# W506E.net
KiCad netlist of a schematic drawn in EAGLE
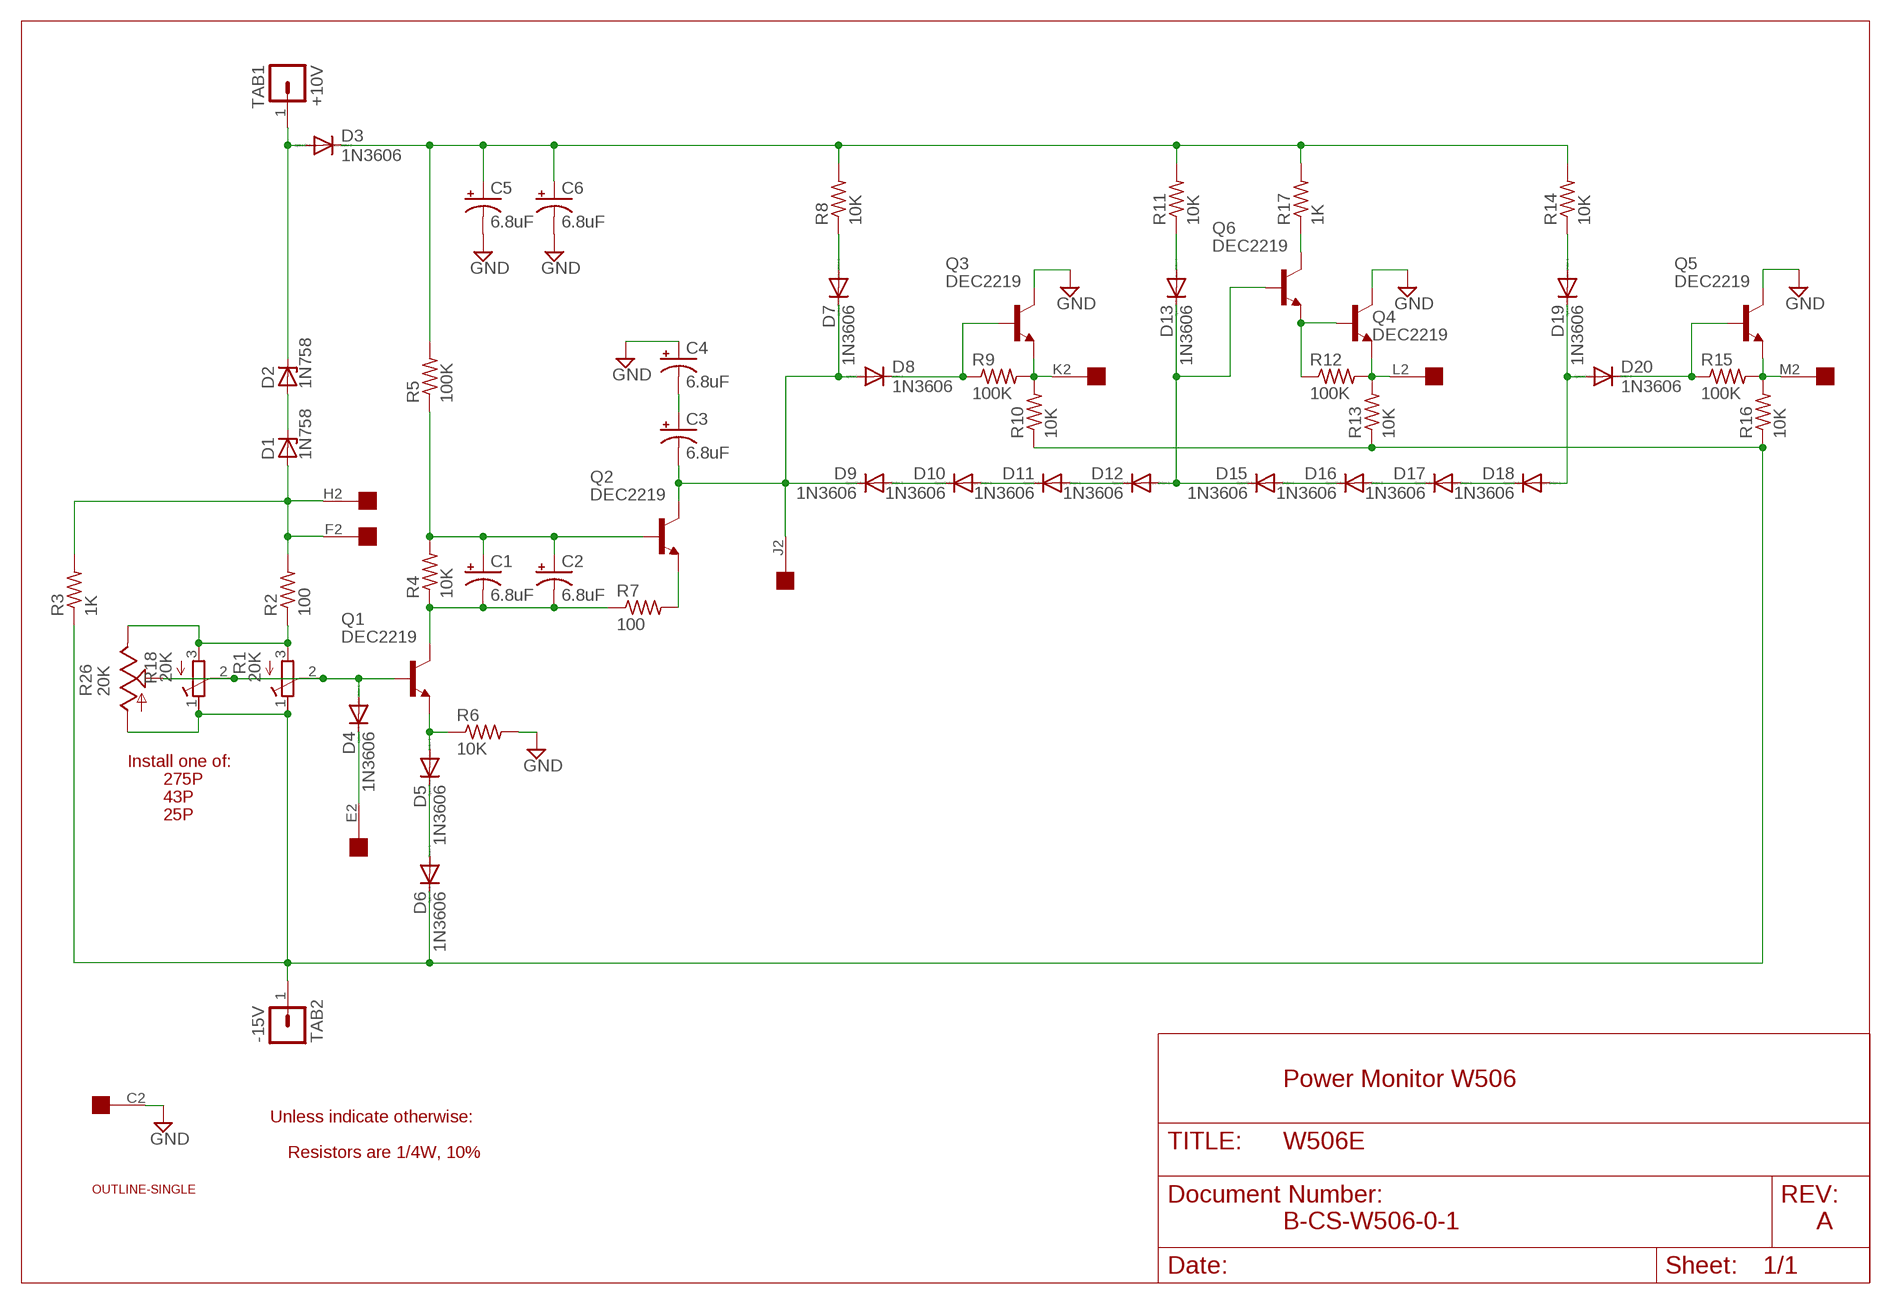
[diagram p0: schematic, sheet 1]

(export (version "E")
  (design (tool "Eeschema 10.0.6"))
  (components
    (comp (ref "C1")
      (value "6.8uF")
      (footprint "eagle-import:E15-5")
      (libsource (lib "eagle-import") (part "CPOL-USE15-5AXIAL"))
    )
    (comp (ref "C2")
      (value "6.8uF")
      (footprint "eagle-import:E15-5")
      (libsource (lib "eagle-import") (part "CPOL-USE15-5AXIAL"))
    )
    (comp (ref "C3")
      (value "6.8uF")
      (footprint "eagle-import:E15-5")
      (libsource (lib "eagle-import") (part "CPOL-USE15-5AXIAL"))
    )
    (comp (ref "C4")
      (value "6.8uF")
      (footprint "eagle-import:E15-5")
      (libsource (lib "eagle-import") (part "CPOL-USE15-5AXIAL"))
    )
    (comp (ref "C5")
      (value "6.8uF")
      (footprint "eagle-import:E15-5")
      (libsource (lib "eagle-import") (part "CPOL-USE15-5AXIAL"))
    )
    (comp (ref "C6")
      (value "6.8uF")
      (footprint "eagle-import:E15-5")
      (libsource (lib "eagle-import") (part "CPOL-USE15-5AXIAL"))
    )
    (comp (ref "D1")
      (value "1N758")
      (footprint "eagle-import:DO35Z10")
      (libsource (lib "eagle-import") (part "ZENER-DIODEDO35Z10"))
    )
    (comp (ref "D2")
      (value "1N758")
      (footprint "eagle-import:DO35Z10")
      (libsource (lib "eagle-import") (part "ZENER-DIODEDO35Z10"))
    )
    (comp (ref "D3")
      (value "1N3606")
      (footprint "eagle-import:DO35-10")
      (libsource (lib "eagle-import") (part "1N4148DO35-10"))
    )
    (comp (ref "D4")
      (value "1N3606")
      (footprint "eagle-import:DO35-10")
      (libsource (lib "eagle-import") (part "1N4148DO35-10"))
    )
    (comp (ref "D5")
      (value "1N3606")
      (footprint "eagle-import:DO35-10")
      (libsource (lib "eagle-import") (part "1N4148DO35-10"))
    )
    (comp (ref "D6")
      (value "1N3606")
      (footprint "eagle-import:DO35-10")
      (libsource (lib "eagle-import") (part "1N4148DO35-10"))
    )
    (comp (ref "D7")
      (value "1N3606")
      (footprint "eagle-import:DO35-10")
      (libsource (lib "eagle-import") (part "1N4148DO35-10"))
    )
    (comp (ref "D8")
      (value "1N3606")
      (footprint "eagle-import:DO35-10")
      (libsource (lib "eagle-import") (part "1N4148DO35-10"))
    )
    (comp (ref "D9")
      (value "1N3606")
      (footprint "eagle-import:DO35-10")
      (libsource (lib "eagle-import") (part "1N4148DO35-10"))
    )
    (comp (ref "D10")
      (value "1N3606")
      (footprint "eagle-import:DO35-10")
      (libsource (lib "eagle-import") (part "1N4148DO35-10"))
    )
    (comp (ref "D11")
      (value "1N3606")
      (footprint "eagle-import:DO35-10")
      (libsource (lib "eagle-import") (part "1N4148DO35-10"))
    )
    (comp (ref "D12")
      (value "1N3606")
      (footprint "eagle-import:DO35-10")
      (libsource (lib "eagle-import") (part "1N4148DO35-10"))
    )
    (comp (ref "D13")
      (value "1N3606")
      (footprint "eagle-import:DO35-10")
      (libsource (lib "eagle-import") (part "1N4148DO35-10"))
    )
    (comp (ref "D15")
      (value "1N3606")
      (footprint "eagle-import:DO35-10")
      (libsource (lib "eagle-import") (part "1N4148DO35-10"))
    )
    (comp (ref "D16")
      (value "1N3606")
      (footprint "eagle-import:DO35-10")
      (libsource (lib "eagle-import") (part "1N4148DO35-10"))
    )
    (comp (ref "D17")
      (value "1N3606")
      (footprint "eagle-import:DO35-10")
      (libsource (lib "eagle-import") (part "1N4148DO35-10"))
    )
    (comp (ref "D18")
      (value "1N3606")
      (footprint "eagle-import:DO35-10")
      (libsource (lib "eagle-import") (part "1N4148DO35-10"))
    )
    (comp (ref "D19")
      (value "1N3606")
      (footprint "eagle-import:DO35-10")
      (libsource (lib "eagle-import") (part "1N4148DO35-10"))
    )
    (comp (ref "D20")
      (value "1N3606")
      (footprint "eagle-import:DO35-10")
      (libsource (lib "eagle-import") (part "1N4148DO35-10"))
    )
    (comp (ref "EDGE")
      (value "EDGE-1")
      (footprint "eagle-import:EDGE-CON1")
      (libsource (lib "eagle-import") (part "EDGE-1"))
    )
    (comp (ref "Q1")
      (value "DEC2219")
      (footprint "eagle-import:TO5")
      (libsource (lib "eagle-import") (part "2N2102"))
    )
    (comp (ref "Q2")
      (value "DEC2219")
      (footprint "eagle-import:TO5")
      (libsource (lib "eagle-import") (part "2N2102"))
    )
    (comp (ref "Q3")
      (value "DEC2219")
      (footprint "eagle-import:TO5")
      (libsource (lib "eagle-import") (part "2N2102"))
    )
    (comp (ref "Q4")
      (value "DEC2219")
      (footprint "eagle-import:TO5")
      (libsource (lib "eagle-import") (part "2N2102"))
    )
    (comp (ref "Q5")
      (value "DEC2219")
      (footprint "eagle-import:TO5")
      (libsource (lib "eagle-import") (part "2N2102"))
    )
    (comp (ref "Q6")
      (value "DEC2219")
      (footprint "eagle-import:TO5")
      (libsource (lib "eagle-import") (part "2N2102"))
    )
    (comp (ref "R1")
      (value "20K")
      (footprint "eagle-import:3006Y")
      (libsource (lib "eagle-import") (part "275P"))
    )
    (comp (ref "R2")
      (value "100")
      (footprint "eagle-import:0207_10")
      (libsource (lib "eagle-import") (part "R-US_0207/10"))
    )
    (comp (ref "R3")
      (value "1K")
      (footprint "eagle-import:0207_10")
      (libsource (lib "eagle-import") (part "R-US_0207/10"))
    )
    (comp (ref "R4")
      (value "10K")
      (footprint "eagle-import:0207_10")
      (libsource (lib "eagle-import") (part "R-US_0207/10"))
    )
    (comp (ref "R5")
      (value "100K")
      (footprint "eagle-import:0207_10")
      (libsource (lib "eagle-import") (part "R-US_0207/10"))
    )
    (comp (ref "R6")
      (value "10K")
      (footprint "eagle-import:0207_10")
      (libsource (lib "eagle-import") (part "R-US_0207/10"))
    )
    (comp (ref "R7")
      (value "100")
      (footprint "eagle-import:0207_10")
      (libsource (lib "eagle-import") (part "R-US_0207/10"))
    )
    (comp (ref "R8")
      (value "10K")
      (footprint "eagle-import:0207_10")
      (libsource (lib "eagle-import") (part "R-US_0207/10"))
    )
    (comp (ref "R9")
      (value "100K")
      (footprint "eagle-import:0207_10")
      (libsource (lib "eagle-import") (part "R-US_0207/10"))
    )
    (comp (ref "R10")
      (value "10K")
      (footprint "eagle-import:0207_10")
      (libsource (lib "eagle-import") (part "R-US_0207/10"))
    )
    (comp (ref "R11")
      (value "10K")
      (footprint "eagle-import:0207_10")
      (libsource (lib "eagle-import") (part "R-US_0207/10"))
    )
    (comp (ref "R12")
      (value "100K")
      (footprint "eagle-import:0207_10")
      (libsource (lib "eagle-import") (part "R-US_0207/10"))
    )
    (comp (ref "R13")
      (value "10K")
      (footprint "eagle-import:0207_10")
      (libsource (lib "eagle-import") (part "R-US_0207/10"))
    )
    (comp (ref "R14")
      (value "10K")
      (footprint "eagle-import:0207_10")
      (libsource (lib "eagle-import") (part "R-US_0207/10"))
    )
    (comp (ref "R15")
      (value "100K")
      (footprint "eagle-import:0207_10")
      (libsource (lib "eagle-import") (part "R-US_0207/10"))
    )
    (comp (ref "R16")
      (value "10K")
      (footprint "eagle-import:0207_10")
      (libsource (lib "eagle-import") (part "R-US_0207/10"))
    )
    (comp (ref "R17")
      (value "1K")
      (footprint "eagle-import:0207_10")
      (libsource (lib "eagle-import") (part "R-US_0207/10"))
    )
    (comp (ref "R18")
      (value "20K")
      (footprint "eagle-import:RTRIM43P")
      (libsource (lib "eagle-import") (part "R-TRIMM43P"))
    )
    (comp (ref "R26")
      (value "20K")
      (footprint "eagle-import:B25P")
      (libsource (lib "eagle-import") (part "TRIM_US-B25P"))
    )
    (comp (ref "TAB1")
      (value "+10V")
      (footprint "eagle-import:SPADELUG")
      (libsource (lib "eagle-import") (part "LUG"))
    )
    (comp (ref "TAB2")
      (value "-15V")
      (footprint "eagle-import:SPADELUG")
      (libsource (lib "eagle-import") (part "LUG"))
    )
    (comp (ref "U$1")
      (value "OUTLINE-SINGLE")
      (footprint "eagle-import:SINGLE")
      (libsource (lib "eagle-import") (part "OUTLINE-SINGLE"))
    )
  )
  (nets
    (net (code "1") (name "GND") (class "Default")
      (node (ref "C4") (pin "+") (pinfunction "+_+") (pintype "passive"))
      (node (ref "C5") (pin "-") (pinfunction "-_-") (pintype "passive"))
      (node (ref "C6") (pin "-") (pinfunction "-_-") (pintype "passive"))
      (node (ref "EDGE") (pin "C2") (pinfunction "1_C2") (pintype "bidirectional"))
      (node (ref "Q3") (pin "3") (pinfunction "C_3") (pintype "passive"))
      (node (ref "Q4") (pin "3") (pinfunction "C_3") (pintype "passive"))
      (node (ref "Q5") (pin "3") (pinfunction "C_3") (pintype "passive"))
      (node (ref "R6") (pin "2") (pinfunction "2_2") (pintype "passive"))
    )
    (net (code "2") (name "Net-(C3-Pad+)") (class "Default")
      (node (ref "C3") (pin "+") (pinfunction "+_+") (pintype "passive"))
      (node (ref "C4") (pin "-") (pinfunction "-_-") (pintype "passive"))
    )
    (net (code "3") (name "Net-(C5-Pad+)") (class "Default")
      (node (ref "C5") (pin "+") (pinfunction "+_+") (pintype "passive"))
      (node (ref "C6") (pin "+") (pinfunction "+_+") (pintype "passive"))
      (node (ref "D3") (pin "C") (pinfunction "C_C") (pintype "passive"))
      (node (ref "R11") (pin "2") (pinfunction "2_2") (pintype "passive"))
      (node (ref "R14") (pin "2") (pinfunction "2_2") (pintype "passive"))
      (node (ref "R17") (pin "2") (pinfunction "2_2") (pintype "passive"))
      (node (ref "R5") (pin "2") (pinfunction "2_2") (pintype "passive"))
      (node (ref "R8") (pin "2") (pinfunction "2_2") (pintype "passive"))
    )
    (net (code "4") (name "Net-(D1-PadC)") (class "Default")
      (node (ref "D1") (pin "C") (pinfunction "C_C") (pintype "passive"))
      (node (ref "D2") (pin "A") (pinfunction "A_A") (pintype "passive"))
    )
    (net (code "5") (name "Net-(D2-PadC)") (class "Default")
      (node (ref "D2") (pin "C") (pinfunction "C_C") (pintype "passive"))
      (node (ref "D3") (pin "A") (pinfunction "A_A") (pintype "passive"))
      (node (ref "TAB1") (pin "1") (pinfunction "1_1") (pintype "passive"))
    )
    (net (code "6") (name "Net-(D5-PadC)") (class "Default")
      (node (ref "D5") (pin "C") (pinfunction "C_C") (pintype "passive"))
      (node (ref "D6") (pin "A") (pinfunction "A_A") (pintype "passive"))
    )
    (net (code "7") (name "Net-(D7-PadA)") (class "Default")
      (node (ref "D7") (pin "A") (pinfunction "A_A") (pintype "passive"))
      (node (ref "R8") (pin "1") (pinfunction "1_1") (pintype "passive"))
    )
    (net (code "8") (name "Net-(D10-PadA)") (class "Default")
      (node (ref "D10") (pin "A") (pinfunction "A_A") (pintype "passive"))
      (node (ref "D11") (pin "C") (pinfunction "C_C") (pintype "passive"))
    )
    (net (code "9") (name "Net-(D10-PadC)") (class "Default")
      (node (ref "D10") (pin "C") (pinfunction "C_C") (pintype "passive"))
      (node (ref "D9") (pin "A") (pinfunction "A_A") (pintype "passive"))
    )
    (net (code "10") (name "Net-(D11-PadA)") (class "Default")
      (node (ref "D11") (pin "A") (pinfunction "A_A") (pintype "passive"))
      (node (ref "D12") (pin "C") (pinfunction "C_C") (pintype "passive"))
    )
    (net (code "11") (name "Net-(D13-PadA)") (class "Default")
      (node (ref "D13") (pin "A") (pinfunction "A_A") (pintype "passive"))
      (node (ref "R11") (pin "1") (pinfunction "1_1") (pintype "passive"))
    )
    (net (code "12") (name "Net-(D15-PadA)") (class "Default")
      (node (ref "D15") (pin "A") (pinfunction "A_A") (pintype "passive"))
      (node (ref "D16") (pin "C") (pinfunction "C_C") (pintype "passive"))
    )
    (net (code "13") (name "Net-(D16-PadA)") (class "Default")
      (node (ref "D16") (pin "A") (pinfunction "A_A") (pintype "passive"))
      (node (ref "D17") (pin "C") (pinfunction "C_C") (pintype "passive"))
    )
    (net (code "14") (name "Net-(D17-PadA)") (class "Default")
      (node (ref "D17") (pin "A") (pinfunction "A_A") (pintype "passive"))
      (node (ref "D18") (pin "C") (pinfunction "C_C") (pintype "passive"))
    )
    (net (code "15") (name "Net-(D18-PadA)") (class "Default")
      (node (ref "D18") (pin "A") (pinfunction "A_A") (pintype "passive"))
      (node (ref "D19") (pin "C") (pinfunction "C_C") (pintype "passive"))
      (node (ref "D20") (pin "A") (pinfunction "A_A") (pintype "passive"))
    )
    (net (code "16") (name "Net-(D19-PadA)") (class "Default")
      (node (ref "D19") (pin "A") (pinfunction "A_A") (pintype "passive"))
      (node (ref "R14") (pin "1") (pinfunction "1_1") (pintype "passive"))
    )
    (net (code "17") (name "Net-(EDGEE-1)") (class "Default")
      (node (ref "D4") (pin "C") (pinfunction "C_C") (pintype "passive"))
      (node (ref "EDGE") (pin "E2") (pinfunction "1_E2") (pintype "bidirectional"))
    )
    (net (code "18") (name "Net-(EDGEF-1)") (class "Default")
      (node (ref "D1") (pin "A") (pinfunction "A_A") (pintype "passive"))
      (node (ref "EDGE") (pin "F2") (pinfunction "1_F2") (pintype "bidirectional"))
      (node (ref "EDGE") (pin "H2") (pinfunction "1_H2") (pintype "bidirectional"))
      (node (ref "R2") (pin "2") (pinfunction "2_2") (pintype "passive"))
      (node (ref "R3") (pin "2") (pinfunction "2_2") (pintype "passive"))
    )
    (net (code "19") (name "Net-(EDGEH-1)") (class "Default")
      (node (ref "C3") (pin "-") (pinfunction "-_-") (pintype "passive"))
      (node (ref "D7") (pin "C") (pinfunction "C_C") (pintype "passive"))
      (node (ref "D8") (pin "A") (pinfunction "A_A") (pintype "passive"))
      (node (ref "D9") (pin "C") (pinfunction "C_C") (pintype "passive"))
      (node (ref "EDGE") (pin "J2") (pinfunction "1_J2") (pintype "bidirectional"))
      (node (ref "Q2") (pin "3") (pinfunction "C_3") (pintype "passive"))
    )
    (net (code "20") (name "Net-(EDGEI-1)") (class "Default")
      (node (ref "EDGE") (pin "K2") (pinfunction "1_K2") (pintype "bidirectional"))
      (node (ref "Q3") (pin "1") (pinfunction "E_1") (pintype "passive"))
      (node (ref "R10") (pin "2") (pinfunction "2_2") (pintype "passive"))
      (node (ref "R9") (pin "2") (pinfunction "2_2") (pintype "passive"))
    )
    (net (code "21") (name "Net-(EDGEJ-1)") (class "Default")
      (node (ref "EDGE") (pin "L2") (pinfunction "1_L2") (pintype "bidirectional"))
      (node (ref "Q4") (pin "1") (pinfunction "E_1") (pintype "passive"))
      (node (ref "R12") (pin "2") (pinfunction "2_2") (pintype "passive"))
      (node (ref "R13") (pin "2") (pinfunction "2_2") (pintype "passive"))
    )
    (net (code "22") (name "Net-(EDGEK-1)") (class "Default")
      (node (ref "EDGE") (pin "M2") (pinfunction "1_M2") (pintype "bidirectional"))
      (node (ref "Q5") (pin "1") (pinfunction "E_1") (pintype "passive"))
      (node (ref "R15") (pin "2") (pinfunction "2_2") (pintype "passive"))
      (node (ref "R16") (pin "2") (pinfunction "2_2") (pintype "passive"))
    )
    (net (code "23") (name "Net-(Q1-B)") (class "Default")
      (node (ref "D4") (pin "A") (pinfunction "A_A") (pintype "passive"))
      (node (ref "Q1") (pin "2") (pinfunction "B_2") (pintype "passive"))
      (node (ref "R1") (pin "2") (pinfunction "S_2") (pintype "passive"))
      (node (ref "R18") (pin "2") (pinfunction "S_2") (pintype "passive"))
      (node (ref "R26") (pin "S") (pinfunction "S_S") (pintype "passive"))
    )
    (net (code "24") (name "Net-(Q1-C)") (class "Default")
      (node (ref "C1") (pin "-") (pinfunction "-_-") (pintype "passive"))
      (node (ref "C2") (pin "-") (pinfunction "-_-") (pintype "passive"))
      (node (ref "Q1") (pin "3") (pinfunction "C_3") (pintype "passive"))
      (node (ref "R4") (pin "1") (pinfunction "1_1") (pintype "passive"))
      (node (ref "R7") (pin "1") (pinfunction "1_1") (pintype "passive"))
    )
    (net (code "25") (name "Net-(Q1-E)") (class "Default")
      (node (ref "D5") (pin "A") (pinfunction "A_A") (pintype "passive"))
      (node (ref "Q1") (pin "1") (pinfunction "E_1") (pintype "passive"))
      (node (ref "R6") (pin "1") (pinfunction "1_1") (pintype "passive"))
    )
    (net (code "26") (name "Net-(Q2-B)") (class "Default")
      (node (ref "C1") (pin "+") (pinfunction "+_+") (pintype "passive"))
      (node (ref "C2") (pin "+") (pinfunction "+_+") (pintype "passive"))
      (node (ref "Q2") (pin "2") (pinfunction "B_2") (pintype "passive"))
      (node (ref "R4") (pin "2") (pinfunction "2_2") (pintype "passive"))
      (node (ref "R5") (pin "1") (pinfunction "1_1") (pintype "passive"))
    )
    (net (code "27") (name "Net-(Q2-E)") (class "Default")
      (node (ref "Q2") (pin "1") (pinfunction "E_1") (pintype "passive"))
      (node (ref "R7") (pin "2") (pinfunction "2_2") (pintype "passive"))
    )
    (net (code "28") (name "Net-(Q3-B)") (class "Default")
      (node (ref "D8") (pin "C") (pinfunction "C_C") (pintype "passive"))
      (node (ref "Q3") (pin "2") (pinfunction "B_2") (pintype "passive"))
      (node (ref "R9") (pin "1") (pinfunction "1_1") (pintype "passive"))
    )
    (net (code "29") (name "Net-(Q4-B)") (class "Default")
      (node (ref "Q4") (pin "2") (pinfunction "B_2") (pintype "passive"))
      (node (ref "Q6") (pin "1") (pinfunction "E_1") (pintype "passive"))
      (node (ref "R12") (pin "1") (pinfunction "1_1") (pintype "passive"))
    )
    (net (code "30") (name "Net-(Q5-B)") (class "Default")
      (node (ref "D20") (pin "C") (pinfunction "C_C") (pintype "passive"))
      (node (ref "Q5") (pin "2") (pinfunction "B_2") (pintype "passive"))
      (node (ref "R15") (pin "1") (pinfunction "1_1") (pintype "passive"))
    )
    (net (code "31") (name "Net-(Q6-B)") (class "Default")
      (node (ref "D12") (pin "A") (pinfunction "A_A") (pintype "passive"))
      (node (ref "D13") (pin "C") (pinfunction "C_C") (pintype "passive"))
      (node (ref "D15") (pin "C") (pinfunction "C_C") (pintype "passive"))
      (node (ref "Q6") (pin "2") (pinfunction "B_2") (pintype "passive"))
    )
    (net (code "32") (name "Net-(Q6-C)") (class "Default")
      (node (ref "Q6") (pin "3") (pinfunction "C_3") (pintype "passive"))
      (node (ref "R17") (pin "1") (pinfunction "1_1") (pintype "passive"))
    )
    (net (code "33") (name "Net-(R1-A)") (class "Default")
      (node (ref "D6") (pin "C") (pinfunction "C_C") (pintype "passive"))
      (node (ref "R1") (pin "1") (pinfunction "A_1") (pintype "passive"))
      (node (ref "R10") (pin "1") (pinfunction "1_1") (pintype "passive"))
      (node (ref "R13") (pin "1") (pinfunction "1_1") (pintype "passive"))
      (node (ref "R16") (pin "1") (pinfunction "1_1") (pintype "passive"))
      (node (ref "R18") (pin "1") (pinfunction "E_1") (pintype "passive"))
      (node (ref "R26") (pin "A") (pinfunction "A_A") (pintype "passive"))
      (node (ref "R3") (pin "1") (pinfunction "1_1") (pintype "passive"))
      (node (ref "TAB2") (pin "1") (pinfunction "1_1") (pintype "passive"))
    )
    (net (code "34") (name "Net-(R1-E)") (class "Default")
      (node (ref "R1") (pin "3") (pinfunction "E_3") (pintype "passive"))
      (node (ref "R18") (pin "3") (pinfunction "A_3") (pintype "passive"))
      (node (ref "R2") (pin "1") (pinfunction "1_1") (pintype "passive"))
      (node (ref "R26") (pin "E") (pinfunction "E_E") (pintype "passive"))
    )
  )
)
